# tarjeta.net
KiCad netlist of a schematic drawn in EAGLE
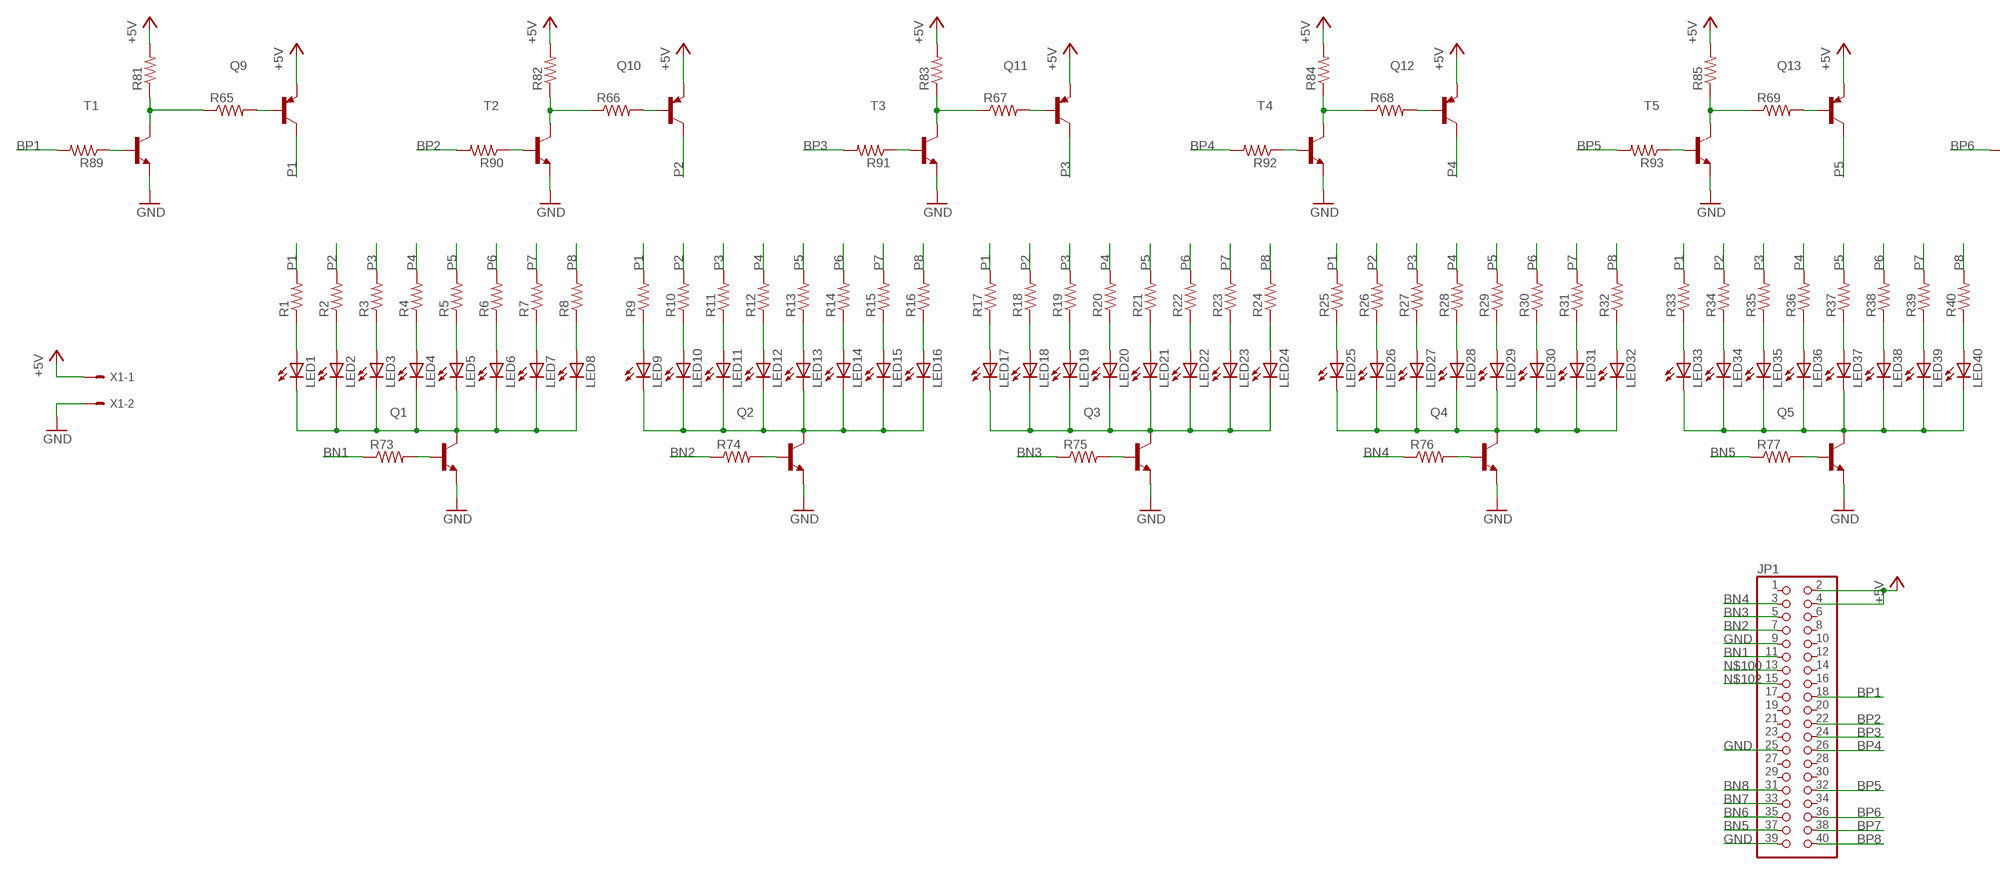
[diagram p0: schematic, sheet 1, part 1 of 2]
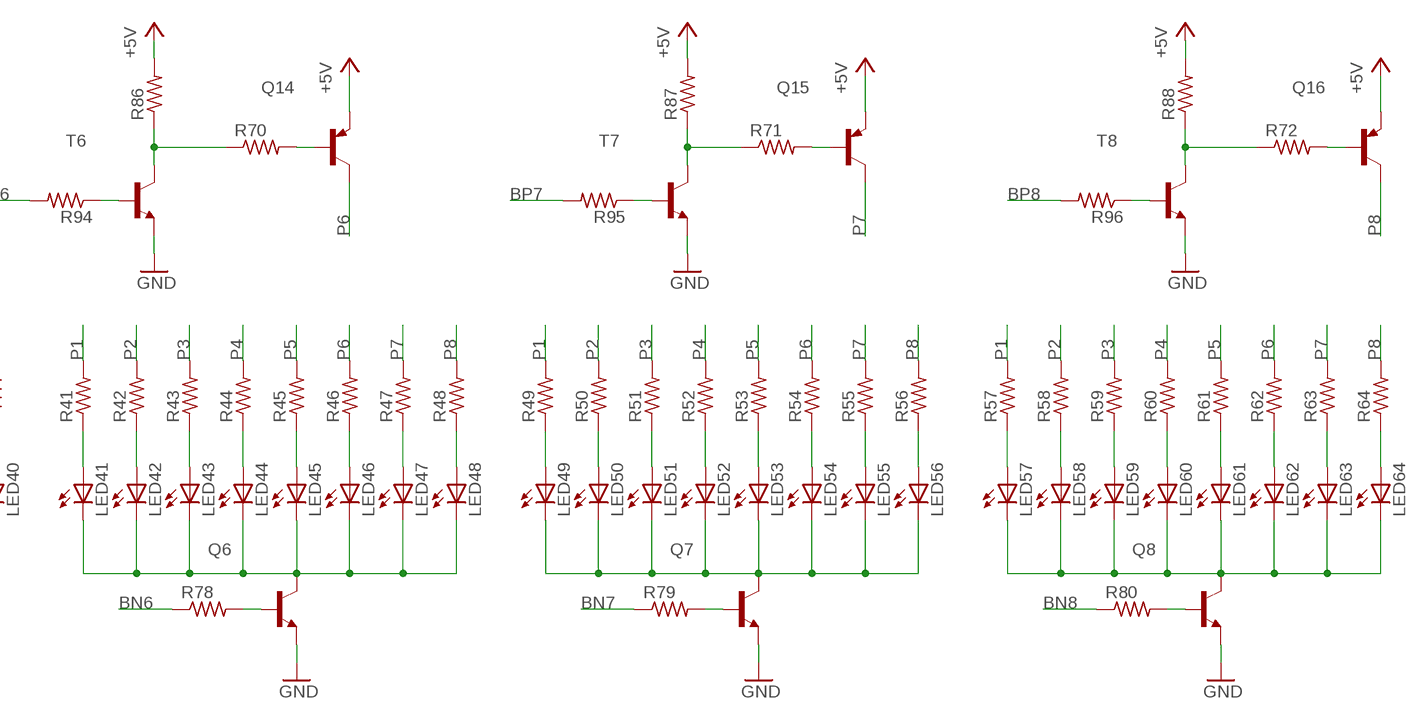
[diagram p1: schematic, sheet 1, part 2 of 2]

(export (version "E")
  (design (tool "Eeschema 10.0.6"))
  (components
    (comp (ref "JP1")
      (value "PINHD-2X20")
      (footprint "eagle-import:2X20")
      (libsource (lib "eagle-import") (part "PINHD-2X20"))
    )
    (comp (ref "LED1")
      (value "LED5MM")
      (footprint "eagle-import:LED5MM")
      (libsource (lib "eagle-import") (part "LED5MM"))
    )
    (comp (ref "LED2")
      (value "LED5MM")
      (footprint "eagle-import:LED5MM")
      (libsource (lib "eagle-import") (part "LED5MM"))
    )
    (comp (ref "LED3")
      (value "LED5MM")
      (footprint "eagle-import:LED5MM")
      (libsource (lib "eagle-import") (part "LED5MM"))
    )
    (comp (ref "LED4")
      (value "LED5MM")
      (footprint "eagle-import:LED5MM")
      (libsource (lib "eagle-import") (part "LED5MM"))
    )
    (comp (ref "LED5")
      (value "LED5MM")
      (footprint "eagle-import:LED5MM")
      (libsource (lib "eagle-import") (part "LED5MM"))
    )
    (comp (ref "LED6")
      (value "LED5MM")
      (footprint "eagle-import:LED5MM")
      (libsource (lib "eagle-import") (part "LED5MM"))
    )
    (comp (ref "LED7")
      (value "LED5MM")
      (footprint "eagle-import:LED5MM")
      (libsource (lib "eagle-import") (part "LED5MM"))
    )
    (comp (ref "LED8")
      (value "LED5MM")
      (footprint "eagle-import:LED5MM")
      (libsource (lib "eagle-import") (part "LED5MM"))
    )
    (comp (ref "LED9")
      (value "LED5MM")
      (footprint "eagle-import:LED5MM")
      (libsource (lib "eagle-import") (part "LED5MM"))
    )
    (comp (ref "LED10")
      (value "LED5MM")
      (footprint "eagle-import:LED5MM")
      (libsource (lib "eagle-import") (part "LED5MM"))
    )
    (comp (ref "LED11")
      (value "LED5MM")
      (footprint "eagle-import:LED5MM")
      (libsource (lib "eagle-import") (part "LED5MM"))
    )
    (comp (ref "LED12")
      (value "LED5MM")
      (footprint "eagle-import:LED5MM")
      (libsource (lib "eagle-import") (part "LED5MM"))
    )
    (comp (ref "LED13")
      (value "LED5MM")
      (footprint "eagle-import:LED5MM")
      (libsource (lib "eagle-import") (part "LED5MM"))
    )
    (comp (ref "LED14")
      (value "LED5MM")
      (footprint "eagle-import:LED5MM")
      (libsource (lib "eagle-import") (part "LED5MM"))
    )
    (comp (ref "LED15")
      (value "LED5MM")
      (footprint "eagle-import:LED5MM")
      (libsource (lib "eagle-import") (part "LED5MM"))
    )
    (comp (ref "LED16")
      (value "LED5MM")
      (footprint "eagle-import:LED5MM")
      (libsource (lib "eagle-import") (part "LED5MM"))
    )
    (comp (ref "LED17")
      (value "LED5MM")
      (footprint "eagle-import:LED5MM")
      (libsource (lib "eagle-import") (part "LED5MM"))
    )
    (comp (ref "LED18")
      (value "LED5MM")
      (footprint "eagle-import:LED5MM")
      (libsource (lib "eagle-import") (part "LED5MM"))
    )
    (comp (ref "LED19")
      (value "LED5MM")
      (footprint "eagle-import:LED5MM")
      (libsource (lib "eagle-import") (part "LED5MM"))
    )
    (comp (ref "LED20")
      (value "LED5MM")
      (footprint "eagle-import:LED5MM")
      (libsource (lib "eagle-import") (part "LED5MM"))
    )
    (comp (ref "LED21")
      (value "LED5MM")
      (footprint "eagle-import:LED5MM")
      (libsource (lib "eagle-import") (part "LED5MM"))
    )
    (comp (ref "LED22")
      (value "LED5MM")
      (footprint "eagle-import:LED5MM")
      (libsource (lib "eagle-import") (part "LED5MM"))
    )
    (comp (ref "LED23")
      (value "LED5MM")
      (footprint "eagle-import:LED5MM")
      (libsource (lib "eagle-import") (part "LED5MM"))
    )
    (comp (ref "LED24")
      (value "LED5MM")
      (footprint "eagle-import:LED5MM")
      (libsource (lib "eagle-import") (part "LED5MM"))
    )
    (comp (ref "LED25")
      (value "LED5MM")
      (footprint "eagle-import:LED5MM")
      (libsource (lib "eagle-import") (part "LED5MM"))
    )
    (comp (ref "LED26")
      (value "LED5MM")
      (footprint "eagle-import:LED5MM")
      (libsource (lib "eagle-import") (part "LED5MM"))
    )
    (comp (ref "LED27")
      (value "LED5MM")
      (footprint "eagle-import:LED5MM")
      (libsource (lib "eagle-import") (part "LED5MM"))
    )
    (comp (ref "LED28")
      (value "LED5MM")
      (footprint "eagle-import:LED5MM")
      (libsource (lib "eagle-import") (part "LED5MM"))
    )
    (comp (ref "LED29")
      (value "LED5MM")
      (footprint "eagle-import:LED5MM")
      (libsource (lib "eagle-import") (part "LED5MM"))
    )
    (comp (ref "LED30")
      (value "LED5MM")
      (footprint "eagle-import:LED5MM")
      (libsource (lib "eagle-import") (part "LED5MM"))
    )
    (comp (ref "LED31")
      (value "LED5MM")
      (footprint "eagle-import:LED5MM")
      (libsource (lib "eagle-import") (part "LED5MM"))
    )
    (comp (ref "LED32")
      (value "LED5MM")
      (footprint "eagle-import:LED5MM")
      (libsource (lib "eagle-import") (part "LED5MM"))
    )
    (comp (ref "LED33")
      (value "LED5MM")
      (footprint "eagle-import:LED5MM")
      (libsource (lib "eagle-import") (part "led_259_LED5MM"))
    )
    (comp (ref "LED34")
      (value "LED5MM")
      (footprint "eagle-import:LED5MM")
      (libsource (lib "eagle-import") (part "LED5MM"))
    )
    (comp (ref "LED35")
      (value "LED5MM")
      (footprint "eagle-import:LED5MM")
      (libsource (lib "eagle-import") (part "LED5MM"))
    )
    (comp (ref "LED36")
      (value "LED5MM")
      (footprint "eagle-import:LED5MM")
      (libsource (lib "eagle-import") (part "LED5MM"))
    )
    (comp (ref "LED37")
      (value "LED5MM")
      (footprint "eagle-import:LED5MM")
      (libsource (lib "eagle-import") (part "LED5MM"))
    )
    (comp (ref "LED38")
      (value "LED5MM")
      (footprint "eagle-import:LED5MM")
      (libsource (lib "eagle-import") (part "LED5MM"))
    )
    (comp (ref "LED39")
      (value "LED5MM")
      (footprint "eagle-import:LED5MM")
      (libsource (lib "eagle-import") (part "LED5MM"))
    )
    (comp (ref "LED40")
      (value "LED5MM")
      (footprint "eagle-import:LED5MM")
      (libsource (lib "eagle-import") (part "LED5MM"))
    )
    (comp (ref "LED41")
      (value "LED5MM")
      (footprint "eagle-import:LED5MM")
      (libsource (lib "eagle-import") (part "LED5MM"))
    )
    (comp (ref "LED42")
      (value "LED5MM")
      (footprint "eagle-import:LED5MM")
      (libsource (lib "eagle-import") (part "LED5MM"))
    )
    (comp (ref "LED43")
      (value "LED5MM")
      (footprint "eagle-import:LED5MM")
      (libsource (lib "eagle-import") (part "LED5MM"))
    )
    (comp (ref "LED44")
      (value "LED5MM")
      (footprint "eagle-import:LED5MM")
      (libsource (lib "eagle-import") (part "LED5MM"))
    )
    (comp (ref "LED45")
      (value "LED5MM")
      (footprint "eagle-import:LED5MM")
      (libsource (lib "eagle-import") (part "LED5MM"))
    )
    (comp (ref "LED46")
      (value "LED5MM")
      (footprint "eagle-import:LED5MM")
      (libsource (lib "eagle-import") (part "LED5MM"))
    )
    (comp (ref "LED47")
      (value "LED5MM")
      (footprint "eagle-import:LED5MM")
      (libsource (lib "eagle-import") (part "LED5MM"))
    )
    (comp (ref "LED48")
      (value "LED5MM")
      (footprint "eagle-import:LED5MM")
      (libsource (lib "eagle-import") (part "LED5MM"))
    )
    (comp (ref "LED49")
      (value "LED5MM")
      (footprint "eagle-import:LED5MM")
      (libsource (lib "eagle-import") (part "LED5MM"))
    )
    (comp (ref "LED50")
      (value "LED5MM")
      (footprint "eagle-import:LED5MM")
      (libsource (lib "eagle-import") (part "LED5MM"))
    )
    (comp (ref "LED51")
      (value "LED5MM")
      (footprint "eagle-import:LED5MM")
      (libsource (lib "eagle-import") (part "LED5MM"))
    )
    (comp (ref "LED52")
      (value "LED5MM")
      (footprint "eagle-import:LED5MM")
      (libsource (lib "eagle-import") (part "LED5MM"))
    )
    (comp (ref "LED53")
      (value "LED5MM")
      (footprint "eagle-import:LED5MM")
      (libsource (lib "eagle-import") (part "LED5MM"))
    )
    (comp (ref "LED54")
      (value "LED5MM")
      (footprint "eagle-import:LED5MM")
      (libsource (lib "eagle-import") (part "LED5MM"))
    )
    (comp (ref "LED55")
      (value "LED5MM")
      (footprint "eagle-import:LED5MM")
      (libsource (lib "eagle-import") (part "LED5MM"))
    )
    (comp (ref "LED56")
      (value "LED5MM")
      (footprint "eagle-import:LED5MM")
      (libsource (lib "eagle-import") (part "LED5MM"))
    )
    (comp (ref "LED57")
      (value "LED5MM")
      (footprint "eagle-import:LED5MM")
      (libsource (lib "eagle-import") (part "LED5MM"))
    )
    (comp (ref "LED58")
      (value "LED5MM")
      (footprint "eagle-import:LED5MM")
      (libsource (lib "eagle-import") (part "LED5MM"))
    )
    (comp (ref "LED59")
      (value "LED5MM")
      (footprint "eagle-import:LED5MM")
      (libsource (lib "eagle-import") (part "LED5MM"))
    )
    (comp (ref "LED60")
      (value "LED5MM")
      (footprint "eagle-import:LED5MM")
      (libsource (lib "eagle-import") (part "LED5MM"))
    )
    (comp (ref "LED61")
      (value "LED5MM")
      (footprint "eagle-import:LED5MM")
      (libsource (lib "eagle-import") (part "LED5MM"))
    )
    (comp (ref "LED62")
      (value "LED5MM")
      (footprint "eagle-import:LED5MM")
      (libsource (lib "eagle-import") (part "LED5MM"))
    )
    (comp (ref "LED63")
      (value "LED5MM")
      (footprint "eagle-import:LED5MM")
      (libsource (lib "eagle-import") (part "LED5MM"))
    )
    (comp (ref "LED64")
      (value "LED5MM")
      (footprint "eagle-import:LED5MM")
      (libsource (lib "eagle-import") (part "LED5MM"))
    )
    (comp (ref "Q1")
      (value "2N2222TO92-CBE")
      (footprint "eagle-import:TO92-CBE")
      (libsource (lib "eagle-import") (part "2N2222TO92-CBE"))
    )
    (comp (ref "Q2")
      (value "2N2222TO92-CBE")
      (footprint "eagle-import:TO92-CBE")
      (libsource (lib "eagle-import") (part "2N2222TO92-CBE"))
    )
    (comp (ref "Q3")
      (value "2N2222TO92-CBE")
      (footprint "eagle-import:TO92-CBE")
      (libsource (lib "eagle-import") (part "2N2222TO92-CBE"))
    )
    (comp (ref "Q4")
      (value "2N2222TO92-CBE")
      (footprint "eagle-import:TO92-CBE")
      (libsource (lib "eagle-import") (part "2N2222TO92-CBE"))
    )
    (comp (ref "Q5")
      (value "2N2222TO92-CBE")
      (footprint "eagle-import:TO92-CBE")
      (libsource (lib "eagle-import") (part "2N2222TO92-CBE"))
    )
    (comp (ref "Q6")
      (value "2N2222TO92-CBE")
      (footprint "eagle-import:TO92-CBE")
      (libsource (lib "eagle-import") (part "2N2222TO92-CBE"))
    )
    (comp (ref "Q7")
      (value "2N2222TO92-CBE")
      (footprint "eagle-import:TO92-CBE")
      (libsource (lib "eagle-import") (part "2N2222TO92-CBE"))
    )
    (comp (ref "Q8")
      (value "2N2222TO92-CBE")
      (footprint "eagle-import:TO92-CBE")
      (libsource (lib "eagle-import") (part "2N2222TO92-CBE"))
    )
    (comp (ref "Q9")
      (value "2N2907TO92-CBE")
      (footprint "eagle-import:TO92-CBE")
      (libsource (lib "eagle-import") (part "2N2907TO92-CBE"))
    )
    (comp (ref "Q10")
      (value "2N2907TO92-CBE")
      (footprint "eagle-import:TO92-CBE")
      (libsource (lib "eagle-import") (part "2N2907TO92-CBE"))
    )
    (comp (ref "Q11")
      (value "2N2907TO92-CBE")
      (footprint "eagle-import:TO92-CBE")
      (libsource (lib "eagle-import") (part "2N2907TO92-CBE"))
    )
    (comp (ref "Q12")
      (value "2N2907TO92-CBE")
      (footprint "eagle-import:TO92-CBE")
      (libsource (lib "eagle-import") (part "2N2907TO92-CBE"))
    )
    (comp (ref "Q13")
      (value "2N2907TO92-CBE")
      (footprint "eagle-import:TO92-CBE")
      (libsource (lib "eagle-import") (part "2N2907TO92-CBE"))
    )
    (comp (ref "Q14")
      (value "2N2907TO92-CBE")
      (footprint "eagle-import:TO92-CBE")
      (libsource (lib "eagle-import") (part "2N2907TO92-CBE"))
    )
    (comp (ref "Q15")
      (value "2N2907TO92-CBE")
      (footprint "eagle-import:TO92-CBE")
      (libsource (lib "eagle-import") (part "2N2907TO92-CBE"))
    )
    (comp (ref "Q16")
      (value "2N2907TO92-CBE")
      (footprint "eagle-import:TO92-CBE")
      (libsource (lib "eagle-import") (part "2N2907TO92-CBE"))
    )
    (comp (ref "R1")
      (value "R-US_0204/7")
      (footprint "eagle-import:0204_7")
      (libsource (lib "eagle-import") (part "R-US_0204/7"))
    )
    (comp (ref "R2")
      (value "R-US_0204/7")
      (footprint "eagle-import:0204_7")
      (libsource (lib "eagle-import") (part "R-US_0204/7"))
    )
    (comp (ref "R3")
      (value "R-US_0204/7")
      (footprint "eagle-import:0204_7")
      (libsource (lib "eagle-import") (part "R-US_0204/7"))
    )
    (comp (ref "R4")
      (value "R-US_0204/7")
      (footprint "eagle-import:0204_7")
      (libsource (lib "eagle-import") (part "R-US_0204/7"))
    )
    (comp (ref "R5")
      (value "R-US_0204/7")
      (footprint "eagle-import:0204_7")
      (libsource (lib "eagle-import") (part "R-US_0204/7"))
    )
    (comp (ref "R6")
      (value "R-US_0204/7")
      (footprint "eagle-import:0204_7")
      (libsource (lib "eagle-import") (part "R-US_0204/7"))
    )
    (comp (ref "R7")
      (value "R-US_0204/7")
      (footprint "eagle-import:0204_7")
      (libsource (lib "eagle-import") (part "R-US_0204/7"))
    )
    (comp (ref "R8")
      (value "R-US_0204/7")
      (footprint "eagle-import:0204_7")
      (libsource (lib "eagle-import") (part "R-US_0204/7"))
    )
    (comp (ref "R9")
      (value "R-US_0204/7")
      (footprint "eagle-import:0204_7")
      (libsource (lib "eagle-import") (part "R-US_0204/7"))
    )
    (comp (ref "R10")
      (value "R-US_0204/7")
      (footprint "eagle-import:0204_7")
      (libsource (lib "eagle-import") (part "R-US_0204/7"))
    )
    (comp (ref "R11")
      (value "R-US_0204/7")
      (footprint "eagle-import:0204_7")
      (libsource (lib "eagle-import") (part "R-US_0204/7"))
    )
    (comp (ref "R12")
      (value "R-US_0204/7")
      (footprint "eagle-import:0204_7")
      (libsource (lib "eagle-import") (part "R-US_0204/7"))
    )
    (comp (ref "R13")
      (value "R-US_0204/7")
      (footprint "eagle-import:0204_7")
      (libsource (lib "eagle-import") (part "R-US_0204/7"))
    )
    (comp (ref "R14")
      (value "R-US_0204/7")
      (footprint "eagle-import:0204_7")
      (libsource (lib "eagle-import") (part "R-US_0204/7"))
    )
    (comp (ref "R15")
      (value "R-US_0204/7")
      (footprint "eagle-import:0204_7")
      (libsource (lib "eagle-import") (part "R-US_0204/7"))
    )
    (comp (ref "R16")
      (value "R-US_0204/7")
      (footprint "eagle-import:0204_7")
      (libsource (lib "eagle-import") (part "R-US_0204/7"))
    )
    (comp (ref "R17")
      (value "R-US_0204/7")
      (footprint "eagle-import:0204_7")
      (libsource (lib "eagle-import") (part "R-US_0204/7"))
    )
    (comp (ref "R18")
      (value "R-US_0204/7")
      (footprint "eagle-import:0204_7")
      (libsource (lib "eagle-import") (part "R-US_0204/7"))
    )
    (comp (ref "R19")
      (value "R-US_0204/7")
      (footprint "eagle-import:0204_7")
      (libsource (lib "eagle-import") (part "R-US_0204/7"))
    )
    (comp (ref "R20")
      (value "R-US_0204/7")
      (footprint "eagle-import:0204_7")
      (libsource (lib "eagle-import") (part "R-US_0204/7"))
    )
    (comp (ref "R21")
      (value "R-US_0204/7")
      (footprint "eagle-import:0204_7")
      (libsource (lib "eagle-import") (part "R-US_0204/7"))
    )
    (comp (ref "R22")
      (value "R-US_0204/7")
      (footprint "eagle-import:0204_7")
      (libsource (lib "eagle-import") (part "R-US_0204/7"))
    )
    (comp (ref "R23")
      (value "R-US_0204/7")
      (footprint "eagle-import:0204_7")
      (libsource (lib "eagle-import") (part "R-US_0204/7"))
    )
    (comp (ref "R24")
      (value "R-US_0204/7")
      (footprint "eagle-import:0204_7")
      (libsource (lib "eagle-import") (part "R-US_0204/7"))
    )
    (comp (ref "R25")
      (value "R-US_0204/7")
      (footprint "eagle-import:0204_7")
      (libsource (lib "eagle-import") (part "R-US_0204/7"))
    )
    (comp (ref "R26")
      (value "R-US_0204/7")
      (footprint "eagle-import:0204_7")
      (libsource (lib "eagle-import") (part "R-US_0204/7"))
    )
    (comp (ref "R27")
      (value "R-US_0204/7")
      (footprint "eagle-import:0204_7")
      (libsource (lib "eagle-import") (part "R-US_0204/7"))
    )
    (comp (ref "R28")
      (value "R-US_0204/7")
      (footprint "eagle-import:0204_7")
      (libsource (lib "eagle-import") (part "R-US_0204/7"))
    )
    (comp (ref "R29")
      (value "R-US_0204/7")
      (footprint "eagle-import:0204_7")
      (libsource (lib "eagle-import") (part "R-US_0204/7"))
    )
    (comp (ref "R30")
      (value "R-US_0204/7")
      (footprint "eagle-import:0204_7")
      (libsource (lib "eagle-import") (part "R-US_0204/7"))
    )
    (comp (ref "R31")
      (value "R-US_0204/7")
      (footprint "eagle-import:0204_7")
      (libsource (lib "eagle-import") (part "R-US_0204/7"))
    )
    (comp (ref "R32")
      (value "R-US_0204/7")
      (footprint "eagle-import:0204_7")
      (libsource (lib "eagle-import") (part "R-US_0204/7"))
    )
    (comp (ref "R33")
      (value "R-US_0204/7")
      (footprint "eagle-import:0204_7")
      (libsource (lib "eagle-import") (part "R-US_0204/7"))
    )
    (comp (ref "R34")
      (value "R-US_0204/7")
      (footprint "eagle-import:0204_7")
      (libsource (lib "eagle-import") (part "R-US_0204/7"))
    )
    (comp (ref "R35")
      (value "R-US_0204/7")
      (footprint "eagle-import:0204_7")
      (libsource (lib "eagle-import") (part "R-US_0204/7"))
    )
    (comp (ref "R36")
      (value "R-US_0204/7")
      (footprint "eagle-import:0204_7")
      (libsource (lib "eagle-import") (part "R-US_0204/7"))
    )
    (comp (ref "R37")
      (value "R-US_0204/7")
      (footprint "eagle-import:0204_7")
      (libsource (lib "eagle-import") (part "R-US_0204/7"))
    )
    (comp (ref "R38")
      (value "R-US_0204/7")
      (footprint "eagle-import:0204_7")
      (libsource (lib "eagle-import") (part "R-US_0204/7"))
    )
    (comp (ref "R39")
      (value "R-US_0204/7")
      (footprint "eagle-import:0204_7")
      (libsource (lib "eagle-import") (part "R-US_0204/7"))
    )
    (comp (ref "R40")
      (value "R-US_0204/7")
      (footprint "eagle-import:0204_7")
      (libsource (lib "eagle-import") (part "R-US_0204/7"))
    )
    (comp (ref "R41")
      (value "R-US_0204/7")
      (footprint "eagle-import:0204_7")
      (libsource (lib "eagle-import") (part "R-US_0204/7"))
    )
    (comp (ref "R42")
      (value "R-US_0204/7")
      (footprint "eagle-import:0204_7")
      (libsource (lib "eagle-import") (part "R-US_0204/7"))
    )
    (comp (ref "R43")
      (value "R-US_0204/7")
      (footprint "eagle-import:0204_7")
      (libsource (lib "eagle-import") (part "R-US_0204/7"))
    )
    (comp (ref "R44")
      (value "R-US_0204/7")
      (footprint "eagle-import:0204_7")
      (libsource (lib "eagle-import") (part "R-US_0204/7"))
    )
    (comp (ref "R45")
      (value "R-US_0204/7")
      (footprint "eagle-import:0204_7")
      (libsource (lib "eagle-import") (part "R-US_0204/7"))
    )
    (comp (ref "R46")
      (value "R-US_0204/7")
      (footprint "eagle-import:0204_7")
      (libsource (lib "eagle-import") (part "R-US_0204/7"))
    )
    (comp (ref "R47")
      (value "R-US_0204/7")
      (footprint "eagle-import:0204_7")
      (libsource (lib "eagle-import") (part "R-US_0204/7"))
    )
    (comp (ref "R48")
      (value "R-US_0204/7")
      (footprint "eagle-import:0204_7")
      (libsource (lib "eagle-import") (part "R-US_0204/7"))
    )
    (comp (ref "R49")
      (value "R-US_0204/7")
      (footprint "eagle-import:0204_7")
      (libsource (lib "eagle-import") (part "R-US_0204/7"))
    )
    (comp (ref "R50")
      (value "R-US_0204/7")
      (footprint "eagle-import:0204_7")
      (libsource (lib "eagle-import") (part "R-US_0204/7"))
    )
    (comp (ref "R51")
      (value "R-US_0204/7")
      (footprint "eagle-import:0204_7")
      (libsource (lib "eagle-import") (part "R-US_0204/7"))
    )
    (comp (ref "R52")
      (value "R-US_0204/7")
      (footprint "eagle-import:0204_7")
      (libsource (lib "eagle-import") (part "R-US_0204/7"))
    )
    (comp (ref "R53")
      (value "R-US_0204/7")
      (footprint "eagle-import:0204_7")
      (libsource (lib "eagle-import") (part "R-US_0204/7"))
    )
    (comp (ref "R54")
      (value "R-US_0204/7")
      (footprint "eagle-import:0204_7")
      (libsource (lib "eagle-import") (part "R-US_0204/7"))
    )
    (comp (ref "R55")
      (value "R-US_0204/7")
      (footprint "eagle-import:0204_7")
      (libsource (lib "eagle-import") (part "R-US_0204/7"))
    )
    (comp (ref "R56")
      (value "R-US_0204/7")
      (footprint "eagle-import:0204_7")
      (libsource (lib "eagle-import") (part "R-US_0204/7"))
    )
    (comp (ref "R57")
      (value "R-US_0204/7")
      (footprint "eagle-import:0204_7")
      (libsource (lib "eagle-import") (part "R-US_0204/7"))
    )
    (comp (ref "R58")
      (value "R-US_0204/7")
      (footprint "eagle-import:0204_7")
      (libsource (lib "eagle-import") (part "R-US_0204/7"))
    )
    (comp (ref "R59")
      (value "R-US_0204/7")
      (footprint "eagle-import:0204_7")
      (libsource (lib "eagle-import") (part "R-US_0204/7"))
    )
    (comp (ref "R60")
      (value "R-US_0204/7")
      (footprint "eagle-import:0204_7")
      (libsource (lib "eagle-import") (part "R-US_0204/7"))
    )
    (comp (ref "R61")
      (value "R-US_0204/7")
      (footprint "eagle-import:0204_7")
      (libsource (lib "eagle-import") (part "R-US_0204/7"))
    )
    (comp (ref "R62")
      (value "R-US_0204/7")
      (footprint "eagle-import:0204_7")
      (libsource (lib "eagle-import") (part "R-US_0204/7"))
    )
    (comp (ref "R63")
      (value "R-US_0204/7")
      (footprint "eagle-import:0204_7")
      (libsource (lib "eagle-import") (part "R-US_0204/7"))
    )
    (comp (ref "R64")
      (value "R-US_0204/7")
      (footprint "eagle-import:0204_7")
      (libsource (lib "eagle-import") (part "R-US_0204/7"))
    )
    (comp (ref "R65")
      (value "R-US_0204/7")
      (footprint "eagle-import:0204_7")
      (libsource (lib "eagle-import") (part "R-US_0204/7"))
    )
    (comp (ref "R66")
      (value "R-US_0204/7")
      (footprint "eagle-import:0204_7")
      (libsource (lib "eagle-import") (part "R-US_0204/7"))
    )
    (comp (ref "R67")
      (value "R-US_0204/7")
      (footprint "eagle-import:0204_7")
      (libsource (lib "eagle-import") (part "R-US_0204/7"))
    )
    (comp (ref "R68")
      (value "R-US_0204/7")
      (footprint "eagle-import:0204_7")
      (libsource (lib "eagle-import") (part "R-US_0204/7"))
    )
    (comp (ref "R69")
      (value "R-US_0204/7")
      (footprint "eagle-import:0204_7")
      (libsource (lib "eagle-import") (part "R-US_0204/7"))
    )
    (comp (ref "R70")
      (value "R-US_0204/7")
      (footprint "eagle-import:0204_7")
      (libsource (lib "eagle-import") (part "R-US_0204/7"))
    )
    (comp (ref "R71")
      (value "R-US_0204/7")
      (footprint "eagle-import:0204_7")
      (libsource (lib "eagle-import") (part "R-US_0204/7"))
    )
    (comp (ref "R72")
      (value "R-US_0204/7")
      (footprint "eagle-import:0204_7")
      (libsource (lib "eagle-import") (part "R-US_0204/7"))
    )
    (comp (ref "R73")
      (value "R-US_0204/7")
      (footprint "eagle-import:0204_7")
      (libsource (lib "eagle-import") (part "R-US_0204/7"))
    )
    (comp (ref "R74")
      (value "R-US_0204/7")
      (footprint "eagle-import:0204_7")
      (libsource (lib "eagle-import") (part "R-US_0204/7"))
    )
    (comp (ref "R75")
      (value "R-US_0204/7")
      (footprint "eagle-import:0204_7")
      (libsource (lib "eagle-import") (part "R-US_0204/7"))
    )
    (comp (ref "R76")
      (value "R-US_0204/7")
      (footprint "eagle-import:0204_7")
      (libsource (lib "eagle-import") (part "R-US_0204/7"))
    )
    (comp (ref "R77")
      (value "R-US_0204/7")
      (footprint "eagle-import:0204_7")
      (libsource (lib "eagle-import") (part "R-US_0204/7"))
    )
    (comp (ref "R78")
      (value "R-US_0204/7")
      (footprint "eagle-import:0204_7")
      (libsource (lib "eagle-import") (part "R-US_0204/7"))
    )
    (comp (ref "R79")
      (value "R-US_0204/7")
      (footprint "eagle-import:0204_7")
      (libsource (lib "eagle-import") (part "R-US_0204/7"))
    )
    (comp (ref "R80")
      (value "R-US_0204/7")
      (footprint "eagle-import:0204_7")
      (libsource (lib "eagle-import") (part "R-US_0204/7"))
    )
    (comp (ref "R81")
      (value "R-US_0204/7")
      (footprint "eagle-import:0204_7")
      (libsource (lib "eagle-import") (part "R-US_0204/7"))
    )
    (comp (ref "R82")
      (value "R-US_0204/7")
      (footprint "eagle-import:0204_7")
      (libsource (lib "eagle-import") (part "R-US_0204/7"))
    )
    (comp (ref "R83")
      (value "R-US_0204/7")
      (footprint "eagle-import:0204_7")
      (libsource (lib "eagle-import") (part "R-US_0204/7"))
    )
    (comp (ref "R84")
      (value "R-US_0204/7")
      (footprint "eagle-import:0204_7")
      (libsource (lib "eagle-import") (part "R-US_0204/7"))
    )
    (comp (ref "R85")
      (value "R-US_0204/7")
      (footprint "eagle-import:0204_7")
      (libsource (lib "eagle-import") (part "R-US_0204/7"))
    )
    (comp (ref "R86")
      (value "R-US_0204/7")
      (footprint "eagle-import:0204_7")
      (libsource (lib "eagle-import") (part "R-US_0204/7"))
    )
    (comp (ref "R87")
      (value "R-US_0204/7")
      (footprint "eagle-import:0204_7")
      (libsource (lib "eagle-import") (part "R-US_0204/7"))
    )
    (comp (ref "R88")
      (value "R-US_0204/7")
      (footprint "eagle-import:0204_7")
      (libsource (lib "eagle-import") (part "R-US_0204/7"))
    )
    (comp (ref "R89")
      (value "R-US_0204/7")
      (footprint "eagle-import:0204_7")
      (libsource (lib "eagle-import") (part "R-US_0204/7"))
    )
    (comp (ref "R90")
      (value "R-US_0204/7")
      (footprint "eagle-import:0204_7")
      (libsource (lib "eagle-import") (part "R-US_0204/7"))
    )
    (comp (ref "R91")
      (value "R-US_0204/7")
      (footprint "eagle-import:0204_7")
      (libsource (lib "eagle-import") (part "R-US_0204/7"))
    )
    (comp (ref "R92")
      (value "R-US_0204/7")
      (footprint "eagle-import:0204_7")
      (libsource (lib "eagle-import") (part "R-US_0204/7"))
    )
    (comp (ref "R93")
      (value "R-US_0204/7")
      (footprint "eagle-import:0204_7")
      (libsource (lib "eagle-import") (part "R-US_0204/7"))
    )
    (comp (ref "R94")
      (value "R-US_0204/7")
      (footprint "eagle-import:0204_7")
      (libsource (lib "eagle-import") (part "R-US_0204/7"))
    )
    (comp (ref "R95")
      (value "R-US_0204/7")
      (footprint "eagle-import:0204_7")
      (libsource (lib "eagle-import") (part "R-US_0204/7"))
    )
    (comp (ref "R96")
      (value "R-US_0204/7")
      (footprint "eagle-import:0204_7")
      (libsource (lib "eagle-import") (part "R-US_0204/7"))
    )
    (comp (ref "T1")
      (value "2N3904TO92-CBE")
      (footprint "eagle-import:TO92-CBE")
      (libsource (lib "eagle-import") (part "2N3904TO92-CBE"))
    )
    (comp (ref "T2")
      (value "2N3904TO92-CBE")
      (footprint "eagle-import:TO92-CBE")
      (libsource (lib "eagle-import") (part "2N3904TO92-CBE"))
    )
    (comp (ref "T3")
      (value "2N3904TO92-CBE")
      (footprint "eagle-import:TO92-CBE")
      (libsource (lib "eagle-import") (part "2N3904TO92-CBE"))
    )
    (comp (ref "T4")
      (value "2N3904TO92-CBE")
      (footprint "eagle-import:TO92-CBE")
      (libsource (lib "eagle-import") (part "2N3904TO92-CBE"))
    )
    (comp (ref "T5")
      (value "2N3904TO92-CBE")
      (footprint "eagle-import:TO92-CBE")
      (libsource (lib "eagle-import") (part "2N3904TO92-CBE"))
    )
    (comp (ref "T6")
      (value "2N3904TO92-CBE")
      (footprint "eagle-import:TO92-CBE")
      (libsource (lib "eagle-import") (part "2N3904TO92-CBE"))
    )
    (comp (ref "T7")
      (value "2N3904TO92-CBE")
      (footprint "eagle-import:TO92-CBE")
      (libsource (lib "eagle-import") (part "2N3904TO92-CBE"))
    )
    (comp (ref "T8")
      (value "2N3904TO92-CBE")
      (footprint "eagle-import:TO92-CBE")
      (libsource (lib "eagle-import") (part "2N3904TO92-CBE"))
    )
    (comp (ref "X1")
      (value "KK-156-2")
      (footprint "eagle-import:KK-156-2")
      (libsource (lib "eagle-import") (part "KK-156-2"))
    )
  )
  (nets
    (net (code "1") (name "+5V") (class "Default")
      (node (ref "JP1") (pin "2") (pinfunction "2_2") (pintype "passive"))
      (node (ref "JP1") (pin "4") (pinfunction "4_4") (pintype "passive"))
      (node (ref "Q10") (pin "E") (pinfunction "E_E") (pintype "passive"))
      (node (ref "Q11") (pin "E") (pinfunction "E_E") (pintype "passive"))
      (node (ref "Q12") (pin "E") (pinfunction "E_E") (pintype "passive"))
      (node (ref "Q13") (pin "E") (pinfunction "E_E") (pintype "passive"))
      (node (ref "Q14") (pin "E") (pinfunction "E_E") (pintype "passive"))
      (node (ref "Q15") (pin "E") (pinfunction "E_E") (pintype "passive"))
      (node (ref "Q16") (pin "E") (pinfunction "E_E") (pintype "passive"))
      (node (ref "Q9") (pin "E") (pinfunction "E_E") (pintype "passive"))
      (node (ref "R81") (pin "2") (pinfunction "2_2") (pintype "passive"))
      (node (ref "R82") (pin "2") (pinfunction "2_2") (pintype "passive"))
      (node (ref "R83") (pin "2") (pinfunction "2_2") (pintype "passive"))
      (node (ref "R84") (pin "2") (pinfunction "2_2") (pintype "passive"))
      (node (ref "R85") (pin "2") (pinfunction "2_2") (pintype "passive"))
      (node (ref "R86") (pin "2") (pinfunction "2_2") (pintype "passive"))
      (node (ref "R87") (pin "2") (pinfunction "2_2") (pintype "passive"))
      (node (ref "R88") (pin "2") (pinfunction "2_2") (pintype "passive"))
      (node (ref "X1") (pin "1") (pinfunction "S_1") (pintype "passive"))
    )
    (net (code "2") (name "/BN1") (class "Default")
      (node (ref "JP1") (pin "11") (pinfunction "11_11") (pintype "passive"))
      (node (ref "R73") (pin "1") (pinfunction "1_1") (pintype "passive"))
    )
    (net (code "3") (name "/BN2") (class "Default")
      (node (ref "JP1") (pin "7") (pinfunction "7_7") (pintype "passive"))
      (node (ref "R74") (pin "1") (pinfunction "1_1") (pintype "passive"))
    )
    (net (code "4") (name "/BN3") (class "Default")
      (node (ref "JP1") (pin "5") (pinfunction "5_5") (pintype "passive"))
      (node (ref "R75") (pin "1") (pinfunction "1_1") (pintype "passive"))
    )
    (net (code "5") (name "/BN4") (class "Default")
      (node (ref "JP1") (pin "3") (pinfunction "3_3") (pintype "passive"))
      (node (ref "R76") (pin "1") (pinfunction "1_1") (pintype "passive"))
    )
    (net (code "6") (name "/BN5") (class "Default")
      (node (ref "JP1") (pin "37") (pinfunction "37_37") (pintype "passive"))
      (node (ref "R77") (pin "1") (pinfunction "1_1") (pintype "passive"))
    )
    (net (code "7") (name "/BN6") (class "Default")
      (node (ref "JP1") (pin "35") (pinfunction "35_35") (pintype "passive"))
      (node (ref "R78") (pin "1") (pinfunction "1_1") (pintype "passive"))
    )
    (net (code "8") (name "/BN7") (class "Default")
      (node (ref "JP1") (pin "33") (pinfunction "33_33") (pintype "passive"))
      (node (ref "R79") (pin "1") (pinfunction "1_1") (pintype "passive"))
    )
    (net (code "9") (name "/BN8") (class "Default")
      (node (ref "JP1") (pin "31") (pinfunction "31_31") (pintype "passive"))
      (node (ref "R80") (pin "1") (pinfunction "1_1") (pintype "passive"))
    )
    (net (code "10") (name "/BP1") (class "Default")
      (node (ref "JP1") (pin "18") (pinfunction "18_18") (pintype "passive"))
      (node (ref "R89") (pin "2") (pinfunction "2_2") (pintype "passive"))
    )
    (net (code "11") (name "/BP2") (class "Default")
      (node (ref "JP1") (pin "22") (pinfunction "22_22") (pintype "passive"))
      (node (ref "R90") (pin "2") (pinfunction "2_2") (pintype "passive"))
    )
    (net (code "12") (name "/BP3") (class "Default")
      (node (ref "JP1") (pin "24") (pinfunction "24_24") (pintype "passive"))
      (node (ref "R91") (pin "2") (pinfunction "2_2") (pintype "passive"))
    )
    (net (code "13") (name "/BP4") (class "Default")
      (node (ref "JP1") (pin "26") (pinfunction "26_26") (pintype "passive"))
      (node (ref "R92") (pin "2") (pinfunction "2_2") (pintype "passive"))
    )
    (net (code "14") (name "/BP5") (class "Default")
      (node (ref "JP1") (pin "32") (pinfunction "32_32") (pintype "passive"))
      (node (ref "R93") (pin "2") (pinfunction "2_2") (pintype "passive"))
    )
    (net (code "15") (name "/BP6") (class "Default")
      (node (ref "JP1") (pin "36") (pinfunction "36_36") (pintype "passive"))
      (node (ref "R94") (pin "2") (pinfunction "2_2") (pintype "passive"))
    )
    (net (code "16") (name "/BP7") (class "Default")
      (node (ref "JP1") (pin "38") (pinfunction "38_38") (pintype "passive"))
      (node (ref "R95") (pin "2") (pinfunction "2_2") (pintype "passive"))
    )
    (net (code "17") (name "/BP8") (class "Default")
      (node (ref "JP1") (pin "40") (pinfunction "40_40") (pintype "passive"))
      (node (ref "R96") (pin "2") (pinfunction "2_2") (pintype "passive"))
    )
    (net (code "18") (name "/N$100") (class "Default")
      (node (ref "JP1") (pin "13") (pinfunction "13_13") (pintype "passive"))
    )
    (net (code "19") (name "/N$102") (class "Default")
      (node (ref "JP1") (pin "15") (pinfunction "15_15") (pintype "passive"))
    )
    (net (code "20") (name "/P1") (class "Default")
      (node (ref "Q9") (pin "C") (pinfunction "C_C") (pintype "passive"))
      (node (ref "R1") (pin "2") (pinfunction "2_2") (pintype "passive"))
      (node (ref "R17") (pin "2") (pinfunction "2_2") (pintype "passive"))
      (node (ref "R25") (pin "2") (pinfunction "2_2") (pintype "passive"))
      (node (ref "R33") (pin "2") (pinfunction "2_2") (pintype "passive"))
      (node (ref "R41") (pin "2") (pinfunction "2_2") (pintype "passive"))
      (node (ref "R49") (pin "2") (pinfunction "2_2") (pintype "passive"))
      (node (ref "R57") (pin "2") (pinfunction "2_2") (pintype "passive"))
      (node (ref "R9") (pin "2") (pinfunction "2_2") (pintype "passive"))
    )
    (net (code "21") (name "/P2") (class "Default")
      (node (ref "Q10") (pin "C") (pinfunction "C_C") (pintype "passive"))
      (node (ref "R10") (pin "2") (pinfunction "2_2") (pintype "passive"))
      (node (ref "R18") (pin "2") (pinfunction "2_2") (pintype "passive"))
      (node (ref "R2") (pin "2") (pinfunction "2_2") (pintype "passive"))
      (node (ref "R26") (pin "2") (pinfunction "2_2") (pintype "passive"))
      (node (ref "R34") (pin "2") (pinfunction "2_2") (pintype "passive"))
      (node (ref "R42") (pin "2") (pinfunction "2_2") (pintype "passive"))
      (node (ref "R50") (pin "2") (pinfunction "2_2") (pintype "passive"))
      (node (ref "R58") (pin "2") (pinfunction "2_2") (pintype "passive"))
    )
    (net (code "22") (name "/P3") (class "Default")
      (node (ref "Q11") (pin "C") (pinfunction "C_C") (pintype "passive"))
      (node (ref "R11") (pin "2") (pinfunction "2_2") (pintype "passive"))
      (node (ref "R19") (pin "2") (pinfunction "2_2") (pintype "passive"))
      (node (ref "R27") (pin "2") (pinfunction "2_2") (pintype "passive"))
      (node (ref "R3") (pin "2") (pinfunction "2_2") (pintype "passive"))
      (node (ref "R35") (pin "2") (pinfunction "2_2") (pintype "passive"))
      (node (ref "R43") (pin "2") (pinfunction "2_2") (pintype "passive"))
      (node (ref "R51") (pin "2") (pinfunction "2_2") (pintype "passive"))
      (node (ref "R59") (pin "2") (pinfunction "2_2") (pintype "passive"))
    )
    (net (code "23") (name "/P4") (class "Default")
      (node (ref "Q12") (pin "C") (pinfunction "C_C") (pintype "passive"))
      (node (ref "R12") (pin "2") (pinfunction "2_2") (pintype "passive"))
      (node (ref "R20") (pin "2") (pinfunction "2_2") (pintype "passive"))
      (node (ref "R28") (pin "2") (pinfunction "2_2") (pintype "passive"))
      (node (ref "R36") (pin "2") (pinfunction "2_2") (pintype "passive"))
      (node (ref "R4") (pin "2") (pinfunction "2_2") (pintype "passive"))
      (node (ref "R44") (pin "2") (pinfunction "2_2") (pintype "passive"))
      (node (ref "R52") (pin "2") (pinfunction "2_2") (pintype "passive"))
      (node (ref "R60") (pin "2") (pinfunction "2_2") (pintype "passive"))
    )
    (net (code "24") (name "/P5") (class "Default")
      (node (ref "Q13") (pin "C") (pinfunction "C_C") (pintype "passive"))
      (node (ref "R13") (pin "2") (pinfunction "2_2") (pintype "passive"))
      (node (ref "R21") (pin "2") (pinfunction "2_2") (pintype "passive"))
      (node (ref "R29") (pin "2") (pinfunction "2_2") (pintype "passive"))
      (node (ref "R37") (pin "2") (pinfunction "2_2") (pintype "passive"))
      (node (ref "R45") (pin "2") (pinfunction "2_2") (pintype "passive"))
      (node (ref "R5") (pin "2") (pinfunction "2_2") (pintype "passive"))
      (node (ref "R53") (pin "2") (pinfunction "2_2") (pintype "passive"))
      (node (ref "R61") (pin "2") (pinfunction "2_2") (pintype "passive"))
    )
    (net (code "25") (name "/P6") (class "Default")
      (node (ref "Q14") (pin "C") (pinfunction "C_C") (pintype "passive"))
      (node (ref "R14") (pin "2") (pinfunction "2_2") (pintype "passive"))
      (node (ref "R22") (pin "2") (pinfunction "2_2") (pintype "passive"))
      (node (ref "R30") (pin "2") (pinfunction "2_2") (pintype "passive"))
      (node (ref "R38") (pin "2") (pinfunction "2_2") (pintype "passive"))
      (node (ref "R46") (pin "2") (pinfunction "2_2") (pintype "passive"))
      (node (ref "R54") (pin "2") (pinfunction "2_2") (pintype "passive"))
      (node (ref "R6") (pin "2") (pinfunction "2_2") (pintype "passive"))
      (node (ref "R62") (pin "2") (pinfunction "2_2") (pintype "passive"))
    )
    (net (code "26") (name "/P7") (class "Default")
      (node (ref "Q15") (pin "C") (pinfunction "C_C") (pintype "passive"))
      (node (ref "R15") (pin "2") (pinfunction "2_2") (pintype "passive"))
      (node (ref "R23") (pin "2") (pinfunction "2_2") (pintype "passive"))
      (node (ref "R31") (pin "2") (pinfunction "2_2") (pintype "passive"))
      (node (ref "R39") (pin "2") (pinfunction "2_2") (pintype "passive"))
      (node (ref "R47") (pin "2") (pinfunction "2_2") (pintype "passive"))
      (node (ref "R55") (pin "2") (pinfunction "2_2") (pintype "passive"))
      (node (ref "R63") (pin "2") (pinfunction "2_2") (pintype "passive"))
      (node (ref "R7") (pin "2") (pinfunction "2_2") (pintype "passive"))
    )
    (net (code "27") (name "/P8") (class "Default")
      (node (ref "Q16") (pin "C") (pinfunction "C_C") (pintype "passive"))
      (node (ref "R16") (pin "2") (pinfunction "2_2") (pintype "passive"))
      (node (ref "R24") (pin "2") (pinfunction "2_2") (pintype "passive"))
      (node (ref "R32") (pin "2") (pinfunction "2_2") (pintype "passive"))
      (node (ref "R40") (pin "2") (pinfunction "2_2") (pintype "passive"))
      (node (ref "R48") (pin "2") (pinfunction "2_2") (pintype "passive"))
      (node (ref "R56") (pin "2") (pinfunction "2_2") (pintype "passive"))
      (node (ref "R64") (pin "2") (pinfunction "2_2") (pintype "passive"))
      (node (ref "R8") (pin "2") (pinfunction "2_2") (pintype "passive"))
    )
    (net (code "28") (name "GND") (class "Default")
      (node (ref "JP1") (pin "25") (pinfunction "25_25") (pintype "passive"))
      (node (ref "JP1") (pin "39") (pinfunction "39_39") (pintype "passive"))
      (node (ref "JP1") (pin "9") (pinfunction "9_9") (pintype "passive"))
      (node (ref "Q1") (pin "E") (pinfunction "E_E") (pintype "passive"))
      (node (ref "Q2") (pin "E") (pinfunction "E_E") (pintype "passive"))
      (node (ref "Q3") (pin "E") (pinfunction "E_E") (pintype "passive"))
      (node (ref "Q4") (pin "E") (pinfunction "E_E") (pintype "passive"))
      (node (ref "Q5") (pin "E") (pinfunction "E_E") (pintype "passive"))
      (node (ref "Q6") (pin "E") (pinfunction "E_E") (pintype "passive"))
      (node (ref "Q7") (pin "E") (pinfunction "E_E") (pintype "passive"))
      (node (ref "Q8") (pin "E") (pinfunction "E_E") (pintype "passive"))
      (node (ref "T1") (pin "E") (pinfunction "E_E") (pintype "passive"))
      (node (ref "T2") (pin "E") (pinfunction "E_E") (pintype "passive"))
      (node (ref "T3") (pin "E") (pinfunction "E_E") (pintype "passive"))
      (node (ref "T4") (pin "E") (pinfunction "E_E") (pintype "passive"))
      (node (ref "T5") (pin "E") (pinfunction "E_E") (pintype "passive"))
      (node (ref "T6") (pin "E") (pinfunction "E_E") (pintype "passive"))
      (node (ref "T7") (pin "E") (pinfunction "E_E") (pintype "passive"))
      (node (ref "T8") (pin "E") (pinfunction "E_E") (pintype "passive"))
      (node (ref "X1") (pin "2") (pinfunction "S_2") (pintype "passive"))
    )
    (net (code "29") (name "Net-(LED1-C)") (class "Default")
      (node (ref "LED1") (pin "K") (pinfunction "C_K") (pintype "passive"))
      (node (ref "LED2") (pin "K") (pinfunction "C_K") (pintype "passive"))
      (node (ref "LED3") (pin "K") (pinfunction "C_K") (pintype "passive"))
      (node (ref "LED4") (pin "K") (pinfunction "C_K") (pintype "passive"))
      (node (ref "LED5") (pin "K") (pinfunction "C_K") (pintype "passive"))
      (node (ref "LED6") (pin "K") (pinfunction "C_K") (pintype "passive"))
      (node (ref "LED7") (pin "K") (pinfunction "C_K") (pintype "passive"))
      (node (ref "LED8") (pin "K") (pinfunction "C_K") (pintype "passive"))
      (node (ref "Q1") (pin "C") (pinfunction "C_C") (pintype "passive"))
    )
    (net (code "30") (name "Net-(LED1-PadA)") (class "Default")
      (node (ref "LED1") (pin "A") (pinfunction "A_A") (pintype "passive"))
      (node (ref "R1") (pin "1") (pinfunction "1_1") (pintype "passive"))
    )
    (net (code "31") (name "Net-(LED2-PadA)") (class "Default")
      (node (ref "LED2") (pin "A") (pinfunction "A_A") (pintype "passive"))
      (node (ref "R2") (pin "1") (pinfunction "1_1") (pintype "passive"))
    )
    (net (code "32") (name "Net-(LED3-PadA)") (class "Default")
      (node (ref "LED3") (pin "A") (pinfunction "A_A") (pintype "passive"))
      (node (ref "R3") (pin "1") (pinfunction "1_1") (pintype "passive"))
    )
    (net (code "33") (name "Net-(LED4-PadA)") (class "Default")
      (node (ref "LED4") (pin "A") (pinfunction "A_A") (pintype "passive"))
      (node (ref "R4") (pin "1") (pinfunction "1_1") (pintype "passive"))
    )
    (net (code "34") (name "Net-(LED5-PadA)") (class "Default")
      (node (ref "LED5") (pin "A") (pinfunction "A_A") (pintype "passive"))
      (node (ref "R5") (pin "1") (pinfunction "1_1") (pintype "passive"))
    )
    (net (code "35") (name "Net-(LED6-PadA)") (class "Default")
      (node (ref "LED6") (pin "A") (pinfunction "A_A") (pintype "passive"))
      (node (ref "R6") (pin "1") (pinfunction "1_1") (pintype "passive"))
    )
    (net (code "36") (name "Net-(LED7-PadA)") (class "Default")
      (node (ref "LED7") (pin "A") (pinfunction "A_A") (pintype "passive"))
      (node (ref "R7") (pin "1") (pinfunction "1_1") (pintype "passive"))
    )
    (net (code "37") (name "Net-(LED8-PadA)") (class "Default")
      (node (ref "LED8") (pin "A") (pinfunction "A_A") (pintype "passive"))
      (node (ref "R8") (pin "1") (pinfunction "1_1") (pintype "passive"))
    )
    (net (code "38") (name "Net-(LED9-PadA)") (class "Default")
      (node (ref "LED9") (pin "A") (pinfunction "A_A") (pintype "passive"))
      (node (ref "R9") (pin "1") (pinfunction "1_1") (pintype "passive"))
    )
    (net (code "39") (name "Net-(LED10-C)") (class "Default")
      (node (ref "LED10") (pin "K") (pinfunction "C_K") (pintype "passive"))
      (node (ref "LED11") (pin "K") (pinfunction "C_K") (pintype "passive"))
      (node (ref "LED12") (pin "K") (pinfunction "C_K") (pintype "passive"))
      (node (ref "LED13") (pin "K") (pinfunction "C_K") (pintype "passive"))
      (node (ref "LED14") (pin "K") (pinfunction "C_K") (pintype "passive"))
      (node (ref "LED15") (pin "K") (pinfunction "C_K") (pintype "passive"))
      (node (ref "LED16") (pin "K") (pinfunction "C_K") (pintype "passive"))
      (node (ref "LED9") (pin "K") (pinfunction "C_K") (pintype "passive"))
      (node (ref "Q2") (pin "C") (pinfunction "C_C") (pintype "passive"))
    )
    (net (code "40") (name "Net-(LED10-PadA)") (class "Default")
      (node (ref "LED10") (pin "A") (pinfunction "A_A") (pintype "passive"))
      (node (ref "R10") (pin "1") (pinfunction "1_1") (pintype "passive"))
    )
    (net (code "41") (name "Net-(LED11-PadA)") (class "Default")
      (node (ref "LED11") (pin "A") (pinfunction "A_A") (pintype "passive"))
      (node (ref "R11") (pin "1") (pinfunction "1_1") (pintype "passive"))
    )
    (net (code "42") (name "Net-(LED12-PadA)") (class "Default")
      (node (ref "LED12") (pin "A") (pinfunction "A_A") (pintype "passive"))
      (node (ref "R12") (pin "1") (pinfunction "1_1") (pintype "passive"))
    )
    (net (code "43") (name "Net-(LED13-PadA)") (class "Default")
      (node (ref "LED13") (pin "A") (pinfunction "A_A") (pintype "passive"))
      (node (ref "R13") (pin "1") (pinfunction "1_1") (pintype "passive"))
    )
    (net (code "44") (name "Net-(LED14-PadA)") (class "Default")
      (node (ref "LED14") (pin "A") (pinfunction "A_A") (pintype "passive"))
      (node (ref "R14") (pin "1") (pinfunction "1_1") (pintype "passive"))
    )
    (net (code "45") (name "Net-(LED15-PadA)") (class "Default")
      (node (ref "LED15") (pin "A") (pinfunction "A_A") (pintype "passive"))
      (node (ref "R15") (pin "1") (pinfunction "1_1") (pintype "passive"))
    )
    (net (code "46") (name "Net-(LED16-PadA)") (class "Default")
      (node (ref "LED16") (pin "A") (pinfunction "A_A") (pintype "passive"))
      (node (ref "R16") (pin "1") (pinfunction "1_1") (pintype "passive"))
    )
    (net (code "47") (name "Net-(LED17-C)") (class "Default")
      (node (ref "LED17") (pin "K") (pinfunction "C_K") (pintype "passive"))
      (node (ref "LED18") (pin "K") (pinfunction "C_K") (pintype "passive"))
      (node (ref "LED19") (pin "K") (pinfunction "C_K") (pintype "passive"))
      (node (ref "LED20") (pin "K") (pinfunction "C_K") (pintype "passive"))
      (node (ref "LED21") (pin "K") (pinfunction "C_K") (pintype "passive"))
      (node (ref "LED22") (pin "K") (pinfunction "C_K") (pintype "passive"))
      (node (ref "LED23") (pin "K") (pinfunction "C_K") (pintype "passive"))
      (node (ref "LED24") (pin "K") (pinfunction "C_K") (pintype "passive"))
      (node (ref "Q3") (pin "C") (pinfunction "C_C") (pintype "passive"))
    )
    (net (code "48") (name "Net-(LED17-PadA)") (class "Default")
      (node (ref "LED17") (pin "A") (pinfunction "A_A") (pintype "passive"))
      (node (ref "R17") (pin "1") (pinfunction "1_1") (pintype "passive"))
    )
    (net (code "49") (name "Net-(LED18-PadA)") (class "Default")
      (node (ref "LED18") (pin "A") (pinfunction "A_A") (pintype "passive"))
      (node (ref "R18") (pin "1") (pinfunction "1_1") (pintype "passive"))
    )
    (net (code "50") (name "Net-(LED19-PadA)") (class "Default")
      (node (ref "LED19") (pin "A") (pinfunction "A_A") (pintype "passive"))
      (node (ref "R19") (pin "1") (pinfunction "1_1") (pintype "passive"))
    )
    (net (code "51") (name "Net-(LED20-PadA)") (class "Default")
      (node (ref "LED20") (pin "A") (pinfunction "A_A") (pintype "passive"))
      (node (ref "R20") (pin "1") (pinfunction "1_1") (pintype "passive"))
    )
    (net (code "52") (name "Net-(LED21-PadA)") (class "Default")
      (node (ref "LED21") (pin "A") (pinfunction "A_A") (pintype "passive"))
      (node (ref "R21") (pin "1") (pinfunction "1_1") (pintype "passive"))
    )
    (net (code "53") (name "Net-(LED22-PadA)") (class "Default")
      (node (ref "LED22") (pin "A") (pinfunction "A_A") (pintype "passive"))
      (node (ref "R22") (pin "1") (pinfunction "1_1") (pintype "passive"))
    )
    (net (code "54") (name "Net-(LED23-PadA)") (class "Default")
      (node (ref "LED23") (pin "A") (pinfunction "A_A") (pintype "passive"))
      (node (ref "R23") (pin "1") (pinfunction "1_1") (pintype "passive"))
    )
    (net (code "55") (name "Net-(LED24-PadA)") (class "Default")
      (node (ref "LED24") (pin "A") (pinfunction "A_A") (pintype "passive"))
      (node (ref "R24") (pin "1") (pinfunction "1_1") (pintype "passive"))
    )
    (net (code "56") (name "Net-(LED25-C)") (class "Default")
      (node (ref "LED25") (pin "K") (pinfunction "C_K") (pintype "passive"))
      (node (ref "LED26") (pin "K") (pinfunction "C_K") (pintype "passive"))
      (node (ref "LED27") (pin "K") (pinfunction "C_K") (pintype "passive"))
      (node (ref "LED28") (pin "K") (pinfunction "C_K") (pintype "passive"))
      (node (ref "LED29") (pin "K") (pinfunction "C_K") (pintype "passive"))
      (node (ref "LED30") (pin "K") (pinfunction "C_K") (pintype "passive"))
      (node (ref "LED31") (pin "K") (pinfunction "C_K") (pintype "passive"))
      (node (ref "LED32") (pin "K") (pinfunction "C_K") (pintype "passive"))
      (node (ref "Q4") (pin "C") (pinfunction "C_C") (pintype "passive"))
    )
    (net (code "57") (name "Net-(LED25-PadA)") (class "Default")
      (node (ref "LED25") (pin "A") (pinfunction "A_A") (pintype "passive"))
      (node (ref "R25") (pin "1") (pinfunction "1_1") (pintype "passive"))
    )
    (net (code "58") (name "Net-(LED26-PadA)") (class "Default")
      (node (ref "LED26") (pin "A") (pinfunction "A_A") (pintype "passive"))
      (node (ref "R26") (pin "1") (pinfunction "1_1") (pintype "passive"))
    )
    (net (code "59") (name "Net-(LED27-PadA)") (class "Default")
      (node (ref "LED27") (pin "A") (pinfunction "A_A") (pintype "passive"))
      (node (ref "R27") (pin "1") (pinfunction "1_1") (pintype "passive"))
    )
    (net (code "60") (name "Net-(LED28-PadA)") (class "Default")
      (node (ref "LED28") (pin "A") (pinfunction "A_A") (pintype "passive"))
      (node (ref "R28") (pin "1") (pinfunction "1_1") (pintype "passive"))
    )
    (net (code "61") (name "Net-(LED29-PadA)") (class "Default")
      (node (ref "LED29") (pin "A") (pinfunction "A_A") (pintype "passive"))
      (node (ref "R29") (pin "1") (pinfunction "1_1") (pintype "passive"))
    )
    (net (code "62") (name "Net-(LED30-PadA)") (class "Default")
      (node (ref "LED30") (pin "A") (pinfunction "A_A") (pintype "passive"))
      (node (ref "R30") (pin "1") (pinfunction "1_1") (pintype "passive"))
    )
    (net (code "63") (name "Net-(LED31-PadA)") (class "Default")
      (node (ref "LED31") (pin "A") (pinfunction "A_A") (pintype "passive"))
      (node (ref "R31") (pin "1") (pinfunction "1_1") (pintype "passive"))
    )
    (net (code "64") (name "Net-(LED32-PadA)") (class "Default")
      (node (ref "LED32") (pin "A") (pinfunction "A_A") (pintype "passive"))
      (node (ref "R32") (pin "1") (pinfunction "1_1") (pintype "passive"))
    )
    (net (code "65") (name "Net-(LED33-C)") (class "Default")
      (node (ref "LED33") (pin "K") (pinfunction "C_K") (pintype "passive"))
      (node (ref "LED34") (pin "K") (pinfunction "C_K") (pintype "passive"))
      (node (ref "LED35") (pin "K") (pinfunction "C_K") (pintype "passive"))
      (node (ref "LED36") (pin "K") (pinfunction "C_K") (pintype "passive"))
      (node (ref "LED37") (pin "K") (pinfunction "C_K") (pintype "passive"))
      (node (ref "LED38") (pin "K") (pinfunction "C_K") (pintype "passive"))
      (node (ref "LED39") (pin "K") (pinfunction "C_K") (pintype "passive"))
      (node (ref "LED40") (pin "K") (pinfunction "C_K") (pintype "passive"))
      (node (ref "Q5") (pin "C") (pinfunction "C_C") (pintype "passive"))
    )
    (net (code "66") (name "Net-(LED33-PadA)") (class "Default")
      (node (ref "LED33") (pin "A") (pinfunction "A_A") (pintype "passive"))
      (node (ref "R33") (pin "1") (pinfunction "1_1") (pintype "passive"))
    )
    (net (code "67") (name "Net-(LED34-PadA)") (class "Default")
      (node (ref "LED34") (pin "A") (pinfunction "A_A") (pintype "passive"))
      (node (ref "R34") (pin "1") (pinfunction "1_1") (pintype "passive"))
    )
    (net (code "68") (name "Net-(LED35-PadA)") (class "Default")
      (node (ref "LED35") (pin "A") (pinfunction "A_A") (pintype "passive"))
      (node (ref "R35") (pin "1") (pinfunction "1_1") (pintype "passive"))
    )
    (net (code "69") (name "Net-(LED36-PadA)") (class "Default")
      (node (ref "LED36") (pin "A") (pinfunction "A_A") (pintype "passive"))
      (node (ref "R36") (pin "1") (pinfunction "1_1") (pintype "passive"))
    )
    (net (code "70") (name "Net-(LED37-PadA)") (class "Default")
      (node (ref "LED37") (pin "A") (pinfunction "A_A") (pintype "passive"))
      (node (ref "R37") (pin "1") (pinfunction "1_1") (pintype "passive"))
    )
    (net (code "71") (name "Net-(LED38-PadA)") (class "Default")
      (node (ref "LED38") (pin "A") (pinfunction "A_A") (pintype "passive"))
      (node (ref "R38") (pin "1") (pinfunction "1_1") (pintype "passive"))
    )
    (net (code "72") (name "Net-(LED39-PadA)") (class "Default")
      (node (ref "LED39") (pin "A") (pinfunction "A_A") (pintype "passive"))
      (node (ref "R39") (pin "1") (pinfunction "1_1") (pintype "passive"))
    )
    (net (code "73") (name "Net-(LED40-PadA)") (class "Default")
      (node (ref "LED40") (pin "A") (pinfunction "A_A") (pintype "passive"))
      (node (ref "R40") (pin "1") (pinfunction "1_1") (pintype "passive"))
    )
    (net (code "74") (name "Net-(LED41-C)") (class "Default")
      (node (ref "LED41") (pin "K") (pinfunction "C_K") (pintype "passive"))
      (node (ref "LED42") (pin "K") (pinfunction "C_K") (pintype "passive"))
      (node (ref "LED43") (pin "K") (pinfunction "C_K") (pintype "passive"))
      (node (ref "LED44") (pin "K") (pinfunction "C_K") (pintype "passive"))
      (node (ref "LED45") (pin "K") (pinfunction "C_K") (pintype "passive"))
      (node (ref "LED46") (pin "K") (pinfunction "C_K") (pintype "passive"))
      (node (ref "LED47") (pin "K") (pinfunction "C_K") (pintype "passive"))
      (node (ref "LED48") (pin "K") (pinfunction "C_K") (pintype "passive"))
      (node (ref "Q6") (pin "C") (pinfunction "C_C") (pintype "passive"))
    )
    (net (code "75") (name "Net-(LED41-PadA)") (class "Default")
      (node (ref "LED41") (pin "A") (pinfunction "A_A") (pintype "passive"))
      (node (ref "R41") (pin "1") (pinfunction "1_1") (pintype "passive"))
    )
    (net (code "76") (name "Net-(LED42-PadA)") (class "Default")
      (node (ref "LED42") (pin "A") (pinfunction "A_A") (pintype "passive"))
      (node (ref "R42") (pin "1") (pinfunction "1_1") (pintype "passive"))
    )
    (net (code "77") (name "Net-(LED43-PadA)") (class "Default")
      (node (ref "LED43") (pin "A") (pinfunction "A_A") (pintype "passive"))
      (node (ref "R43") (pin "1") (pinfunction "1_1") (pintype "passive"))
    )
    (net (code "78") (name "Net-(LED44-PadA)") (class "Default")
      (node (ref "LED44") (pin "A") (pinfunction "A_A") (pintype "passive"))
      (node (ref "R44") (pin "1") (pinfunction "1_1") (pintype "passive"))
    )
    (net (code "79") (name "Net-(LED45-PadA)") (class "Default")
      (node (ref "LED45") (pin "A") (pinfunction "A_A") (pintype "passive"))
      (node (ref "R45") (pin "1") (pinfunction "1_1") (pintype "passive"))
    )
    (net (code "80") (name "Net-(LED46-PadA)") (class "Default")
      (node (ref "LED46") (pin "A") (pinfunction "A_A") (pintype "passive"))
      (node (ref "R46") (pin "1") (pinfunction "1_1") (pintype "passive"))
    )
    (net (code "81") (name "Net-(LED47-PadA)") (class "Default")
      (node (ref "LED47") (pin "A") (pinfunction "A_A") (pintype "passive"))
      (node (ref "R47") (pin "1") (pinfunction "1_1") (pintype "passive"))
    )
    (net (code "82") (name "Net-(LED48-PadA)") (class "Default")
      (node (ref "LED48") (pin "A") (pinfunction "A_A") (pintype "passive"))
      (node (ref "R48") (pin "1") (pinfunction "1_1") (pintype "passive"))
    )
    (net (code "83") (name "Net-(LED49-C)") (class "Default")
      (node (ref "LED49") (pin "K") (pinfunction "C_K") (pintype "passive"))
      (node (ref "LED50") (pin "K") (pinfunction "C_K") (pintype "passive"))
      (node (ref "LED51") (pin "K") (pinfunction "C_K") (pintype "passive"))
      (node (ref "LED52") (pin "K") (pinfunction "C_K") (pintype "passive"))
      (node (ref "LED53") (pin "K") (pinfunction "C_K") (pintype "passive"))
      (node (ref "LED54") (pin "K") (pinfunction "C_K") (pintype "passive"))
      (node (ref "LED55") (pin "K") (pinfunction "C_K") (pintype "passive"))
      (node (ref "LED56") (pin "K") (pinfunction "C_K") (pintype "passive"))
      (node (ref "Q7") (pin "C") (pinfunction "C_C") (pintype "passive"))
    )
    (net (code "84") (name "Net-(LED49-PadA)") (class "Default")
      (node (ref "LED49") (pin "A") (pinfunction "A_A") (pintype "passive"))
      (node (ref "R49") (pin "1") (pinfunction "1_1") (pintype "passive"))
    )
    (net (code "85") (name "Net-(LED50-PadA)") (class "Default")
      (node (ref "LED50") (pin "A") (pinfunction "A_A") (pintype "passive"))
      (node (ref "R50") (pin "1") (pinfunction "1_1") (pintype "passive"))
    )
    (net (code "86") (name "Net-(LED51-PadA)") (class "Default")
      (node (ref "LED51") (pin "A") (pinfunction "A_A") (pintype "passive"))
      (node (ref "R51") (pin "1") (pinfunction "1_1") (pintype "passive"))
    )
    (net (code "87") (name "Net-(LED52-PadA)") (class "Default")
      (node (ref "LED52") (pin "A") (pinfunction "A_A") (pintype "passive"))
      (node (ref "R52") (pin "1") (pinfunction "1_1") (pintype "passive"))
    )
    (net (code "88") (name "Net-(LED53-PadA)") (class "Default")
      (node (ref "LED53") (pin "A") (pinfunction "A_A") (pintype "passive"))
      (node (ref "R53") (pin "1") (pinfunction "1_1") (pintype "passive"))
    )
    (net (code "89") (name "Net-(LED54-PadA)") (class "Default")
      (node (ref "LED54") (pin "A") (pinfunction "A_A") (pintype "passive"))
      (node (ref "R54") (pin "1") (pinfunction "1_1") (pintype "passive"))
    )
    (net (code "90") (name "Net-(LED55-PadA)") (class "Default")
      (node (ref "LED55") (pin "A") (pinfunction "A_A") (pintype "passive"))
      (node (ref "R55") (pin "1") (pinfunction "1_1") (pintype "passive"))
    )
    (net (code "91") (name "Net-(LED56-PadA)") (class "Default")
      (node (ref "LED56") (pin "A") (pinfunction "A_A") (pintype "passive"))
      (node (ref "R56") (pin "1") (pinfunction "1_1") (pintype "passive"))
    )
    (net (code "92") (name "Net-(LED57-C)") (class "Default")
      (node (ref "LED57") (pin "K") (pinfunction "C_K") (pintype "passive"))
      (node (ref "LED58") (pin "K") (pinfunction "C_K") (pintype "passive"))
      (node (ref "LED59") (pin "K") (pinfunction "C_K") (pintype "passive"))
      (node (ref "LED60") (pin "K") (pinfunction "C_K") (pintype "passive"))
      (node (ref "LED61") (pin "K") (pinfunction "C_K") (pintype "passive"))
      (node (ref "LED62") (pin "K") (pinfunction "C_K") (pintype "passive"))
      (node (ref "LED63") (pin "K") (pinfunction "C_K") (pintype "passive"))
      (node (ref "LED64") (pin "K") (pinfunction "C_K") (pintype "passive"))
      (node (ref "Q8") (pin "C") (pinfunction "C_C") (pintype "passive"))
    )
    (net (code "93") (name "Net-(LED57-PadA)") (class "Default")
      (node (ref "LED57") (pin "A") (pinfunction "A_A") (pintype "passive"))
      (node (ref "R57") (pin "1") (pinfunction "1_1") (pintype "passive"))
    )
    (net (code "94") (name "Net-(LED58-PadA)") (class "Default")
      (node (ref "LED58") (pin "A") (pinfunction "A_A") (pintype "passive"))
      (node (ref "R58") (pin "1") (pinfunction "1_1") (pintype "passive"))
    )
    (net (code "95") (name "Net-(LED59-PadA)") (class "Default")
      (node (ref "LED59") (pin "A") (pinfunction "A_A") (pintype "passive"))
      (node (ref "R59") (pin "1") (pinfunction "1_1") (pintype "passive"))
    )
    (net (code "96") (name "Net-(LED60-PadA)") (class "Default")
      (node (ref "LED60") (pin "A") (pinfunction "A_A") (pintype "passive"))
      (node (ref "R60") (pin "1") (pinfunction "1_1") (pintype "passive"))
    )
    (net (code "97") (name "Net-(LED61-PadA)") (class "Default")
      (node (ref "LED61") (pin "A") (pinfunction "A_A") (pintype "passive"))
      (node (ref "R61") (pin "1") (pinfunction "1_1") (pintype "passive"))
    )
    (net (code "98") (name "Net-(LED62-PadA)") (class "Default")
      (node (ref "LED62") (pin "A") (pinfunction "A_A") (pintype "passive"))
      (node (ref "R62") (pin "1") (pinfunction "1_1") (pintype "passive"))
    )
    (net (code "99") (name "Net-(LED63-PadA)") (class "Default")
      (node (ref "LED63") (pin "A") (pinfunction "A_A") (pintype "passive"))
      (node (ref "R63") (pin "1") (pinfunction "1_1") (pintype "passive"))
    )
    (net (code "100") (name "Net-(LED64-PadA)") (class "Default")
      (node (ref "LED64") (pin "A") (pinfunction "A_A") (pintype "passive"))
      (node (ref "R64") (pin "1") (pinfunction "1_1") (pintype "passive"))
    )
    (net (code "101") (name "Net-(Q1-PadB)") (class "Default")
      (node (ref "Q1") (pin "B") (pinfunction "B_B") (pintype "passive"))
      (node (ref "R73") (pin "2") (pinfunction "2_2") (pintype "passive"))
    )
    (net (code "102") (name "Net-(Q2-PadB)") (class "Default")
      (node (ref "Q2") (pin "B") (pinfunction "B_B") (pintype "passive"))
      (node (ref "R74") (pin "2") (pinfunction "2_2") (pintype "passive"))
    )
    (net (code "103") (name "Net-(Q3-PadB)") (class "Default")
      (node (ref "Q3") (pin "B") (pinfunction "B_B") (pintype "passive"))
      (node (ref "R75") (pin "2") (pinfunction "2_2") (pintype "passive"))
    )
    (net (code "104") (name "Net-(Q4-PadB)") (class "Default")
      (node (ref "Q4") (pin "B") (pinfunction "B_B") (pintype "passive"))
      (node (ref "R76") (pin "2") (pinfunction "2_2") (pintype "passive"))
    )
    (net (code "105") (name "Net-(Q5-PadB)") (class "Default")
      (node (ref "Q5") (pin "B") (pinfunction "B_B") (pintype "passive"))
      (node (ref "R77") (pin "2") (pinfunction "2_2") (pintype "passive"))
    )
    (net (code "106") (name "Net-(Q6-PadB)") (class "Default")
      (node (ref "Q6") (pin "B") (pinfunction "B_B") (pintype "passive"))
      (node (ref "R78") (pin "2") (pinfunction "2_2") (pintype "passive"))
    )
    (net (code "107") (name "Net-(Q7-PadB)") (class "Default")
      (node (ref "Q7") (pin "B") (pinfunction "B_B") (pintype "passive"))
      (node (ref "R79") (pin "2") (pinfunction "2_2") (pintype "passive"))
    )
    (net (code "108") (name "Net-(Q8-PadB)") (class "Default")
      (node (ref "Q8") (pin "B") (pinfunction "B_B") (pintype "passive"))
      (node (ref "R80") (pin "2") (pinfunction "2_2") (pintype "passive"))
    )
    (net (code "109") (name "Net-(Q9-PadB)") (class "Default")
      (node (ref "Q9") (pin "B") (pinfunction "B_B") (pintype "passive"))
      (node (ref "R65") (pin "2") (pinfunction "2_2") (pintype "passive"))
    )
    (net (code "110") (name "Net-(Q10-PadB)") (class "Default")
      (node (ref "Q10") (pin "B") (pinfunction "B_B") (pintype "passive"))
      (node (ref "R66") (pin "2") (pinfunction "2_2") (pintype "passive"))
    )
    (net (code "111") (name "Net-(Q11-PadB)") (class "Default")
      (node (ref "Q11") (pin "B") (pinfunction "B_B") (pintype "passive"))
      (node (ref "R67") (pin "2") (pinfunction "2_2") (pintype "passive"))
    )
    (net (code "112") (name "Net-(Q12-PadB)") (class "Default")
      (node (ref "Q12") (pin "B") (pinfunction "B_B") (pintype "passive"))
      (node (ref "R68") (pin "2") (pinfunction "2_2") (pintype "passive"))
    )
    (net (code "113") (name "Net-(Q13-PadB)") (class "Default")
      (node (ref "Q13") (pin "B") (pinfunction "B_B") (pintype "passive"))
      (node (ref "R69") (pin "2") (pinfunction "2_2") (pintype "passive"))
    )
    (net (code "114") (name "Net-(Q14-PadB)") (class "Default")
      (node (ref "Q14") (pin "B") (pinfunction "B_B") (pintype "passive"))
      (node (ref "R70") (pin "2") (pinfunction "2_2") (pintype "passive"))
    )
    (net (code "115") (name "Net-(Q15-PadB)") (class "Default")
      (node (ref "Q15") (pin "B") (pinfunction "B_B") (pintype "passive"))
      (node (ref "R71") (pin "2") (pinfunction "2_2") (pintype "passive"))
    )
    (net (code "116") (name "Net-(Q16-PadB)") (class "Default")
      (node (ref "Q16") (pin "B") (pinfunction "B_B") (pintype "passive"))
      (node (ref "R72") (pin "2") (pinfunction "2_2") (pintype "passive"))
    )
    (net (code "117") (name "Net-(R65-Pad1)") (class "Default")
      (node (ref "R65") (pin "1") (pinfunction "1_1") (pintype "passive"))
      (node (ref "R81") (pin "1") (pinfunction "1_1") (pintype "passive"))
      (node (ref "T1") (pin "C") (pinfunction "C_C") (pintype "passive"))
    )
    (net (code "118") (name "Net-(R66-Pad1)") (class "Default")
      (node (ref "R66") (pin "1") (pinfunction "1_1") (pintype "passive"))
      (node (ref "R82") (pin "1") (pinfunction "1_1") (pintype "passive"))
      (node (ref "T2") (pin "C") (pinfunction "C_C") (pintype "passive"))
    )
    (net (code "119") (name "Net-(R67-Pad1)") (class "Default")
      (node (ref "R67") (pin "1") (pinfunction "1_1") (pintype "passive"))
      (node (ref "R83") (pin "1") (pinfunction "1_1") (pintype "passive"))
      (node (ref "T3") (pin "C") (pinfunction "C_C") (pintype "passive"))
    )
    (net (code "120") (name "Net-(R68-Pad1)") (class "Default")
      (node (ref "R68") (pin "1") (pinfunction "1_1") (pintype "passive"))
      (node (ref "R84") (pin "1") (pinfunction "1_1") (pintype "passive"))
      (node (ref "T4") (pin "C") (pinfunction "C_C") (pintype "passive"))
    )
    (net (code "121") (name "Net-(R69-Pad1)") (class "Default")
      (node (ref "R69") (pin "1") (pinfunction "1_1") (pintype "passive"))
      (node (ref "R85") (pin "1") (pinfunction "1_1") (pintype "passive"))
      (node (ref "T5") (pin "C") (pinfunction "C_C") (pintype "passive"))
    )
    (net (code "122") (name "Net-(R70-Pad1)") (class "Default")
      (node (ref "R70") (pin "1") (pinfunction "1_1") (pintype "passive"))
      (node (ref "R86") (pin "1") (pinfunction "1_1") (pintype "passive"))
      (node (ref "T6") (pin "C") (pinfunction "C_C") (pintype "passive"))
    )
    (net (code "123") (name "Net-(R71-Pad1)") (class "Default")
      (node (ref "R71") (pin "1") (pinfunction "1_1") (pintype "passive"))
      (node (ref "R87") (pin "1") (pinfunction "1_1") (pintype "passive"))
      (node (ref "T7") (pin "C") (pinfunction "C_C") (pintype "passive"))
    )
    (net (code "124") (name "Net-(R72-Pad1)") (class "Default")
      (node (ref "R72") (pin "1") (pinfunction "1_1") (pintype "passive"))
      (node (ref "R88") (pin "1") (pinfunction "1_1") (pintype "passive"))
      (node (ref "T8") (pin "C") (pinfunction "C_C") (pintype "passive"))
    )
    (net (code "125") (name "Net-(R89-Pad1)") (class "Default")
      (node (ref "R89") (pin "1") (pinfunction "1_1") (pintype "passive"))
      (node (ref "T1") (pin "B") (pinfunction "B_B") (pintype "passive"))
    )
    (net (code "126") (name "Net-(R90-Pad1)") (class "Default")
      (node (ref "R90") (pin "1") (pinfunction "1_1") (pintype "passive"))
      (node (ref "T2") (pin "B") (pinfunction "B_B") (pintype "passive"))
    )
    (net (code "127") (name "Net-(R91-Pad1)") (class "Default")
      (node (ref "R91") (pin "1") (pinfunction "1_1") (pintype "passive"))
      (node (ref "T3") (pin "B") (pinfunction "B_B") (pintype "passive"))
    )
    (net (code "128") (name "Net-(R92-Pad1)") (class "Default")
      (node (ref "R92") (pin "1") (pinfunction "1_1") (pintype "passive"))
      (node (ref "T4") (pin "B") (pinfunction "B_B") (pintype "passive"))
    )
    (net (code "129") (name "Net-(R93-Pad1)") (class "Default")
      (node (ref "R93") (pin "1") (pinfunction "1_1") (pintype "passive"))
      (node (ref "T5") (pin "B") (pinfunction "B_B") (pintype "passive"))
    )
    (net (code "130") (name "Net-(R94-Pad1)") (class "Default")
      (node (ref "R94") (pin "1") (pinfunction "1_1") (pintype "passive"))
      (node (ref "T6") (pin "B") (pinfunction "B_B") (pintype "passive"))
    )
    (net (code "131") (name "Net-(R95-Pad1)") (class "Default")
      (node (ref "R95") (pin "1") (pinfunction "1_1") (pintype "passive"))
      (node (ref "T7") (pin "B") (pinfunction "B_B") (pintype "passive"))
    )
    (net (code "132") (name "Net-(R96-Pad1)") (class "Default")
      (node (ref "R96") (pin "1") (pinfunction "1_1") (pintype "passive"))
      (node (ref "T8") (pin "B") (pinfunction "B_B") (pintype "passive"))
    )
    (net (code "133") (name "unconnected-(JP1-Pad1)") (class "Default")
      (node (ref "JP1") (pin "1") (pinfunction "1_1") (pintype "passive"))
    )
    (net (code "134") (name "unconnected-(JP1-Pad6)") (class "Default")
      (node (ref "JP1") (pin "6") (pinfunction "6_6") (pintype "passive"))
    )
    (net (code "135") (name "unconnected-(JP1-Pad8)") (class "Default")
      (node (ref "JP1") (pin "8") (pinfunction "8_8") (pintype "passive"))
    )
    (net (code "136") (name "unconnected-(JP1-Pad10)") (class "Default")
      (node (ref "JP1") (pin "10") (pinfunction "10_10") (pintype "passive"))
    )
    (net (code "137") (name "unconnected-(JP1-Pad12)") (class "Default")
      (node (ref "JP1") (pin "12") (pinfunction "12_12") (pintype "passive"))
    )
    (net (code "138") (name "unconnected-(JP1-Pad14)") (class "Default")
      (node (ref "JP1") (pin "14") (pinfunction "14_14") (pintype "passive"))
    )
    (net (code "139") (name "unconnected-(JP1-Pad16)") (class "Default")
      (node (ref "JP1") (pin "16") (pinfunction "16_16") (pintype "passive"))
    )
    (net (code "140") (name "unconnected-(JP1-Pad17)") (class "Default")
      (node (ref "JP1") (pin "17") (pinfunction "17_17") (pintype "passive"))
    )
    (net (code "141") (name "unconnected-(JP1-Pad19)") (class "Default")
      (node (ref "JP1") (pin "19") (pinfunction "19_19") (pintype "passive"))
    )
    (net (code "142") (name "unconnected-(JP1-Pad20)") (class "Default")
      (node (ref "JP1") (pin "20") (pinfunction "20_20") (pintype "passive"))
    )
    (net (code "143") (name "unconnected-(JP1-Pad21)") (class "Default")
      (node (ref "JP1") (pin "21") (pinfunction "21_21") (pintype "passive"))
    )
    (net (code "144") (name "unconnected-(JP1-Pad23)") (class "Default")
      (node (ref "JP1") (pin "23") (pinfunction "23_23") (pintype "passive"))
    )
    (net (code "145") (name "unconnected-(JP1-Pad27)") (class "Default")
      (node (ref "JP1") (pin "27") (pinfunction "27_27") (pintype "passive"))
    )
    (net (code "146") (name "unconnected-(JP1-Pad28)") (class "Default")
      (node (ref "JP1") (pin "28") (pinfunction "28_28") (pintype "passive"))
    )
    (net (code "147") (name "unconnected-(JP1-Pad29)") (class "Default")
      (node (ref "JP1") (pin "29") (pinfunction "29_29") (pintype "passive"))
    )
    (net (code "148") (name "unconnected-(JP1-Pad30)") (class "Default")
      (node (ref "JP1") (pin "30") (pinfunction "30_30") (pintype "passive"))
    )
    (net (code "149") (name "unconnected-(JP1-Pad34)") (class "Default")
      (node (ref "JP1") (pin "34") (pinfunction "34_34") (pintype "passive"))
    )
  )
)
